# SkateboardIntegrated.net
KiCad netlist of a schematic drawn in EAGLE
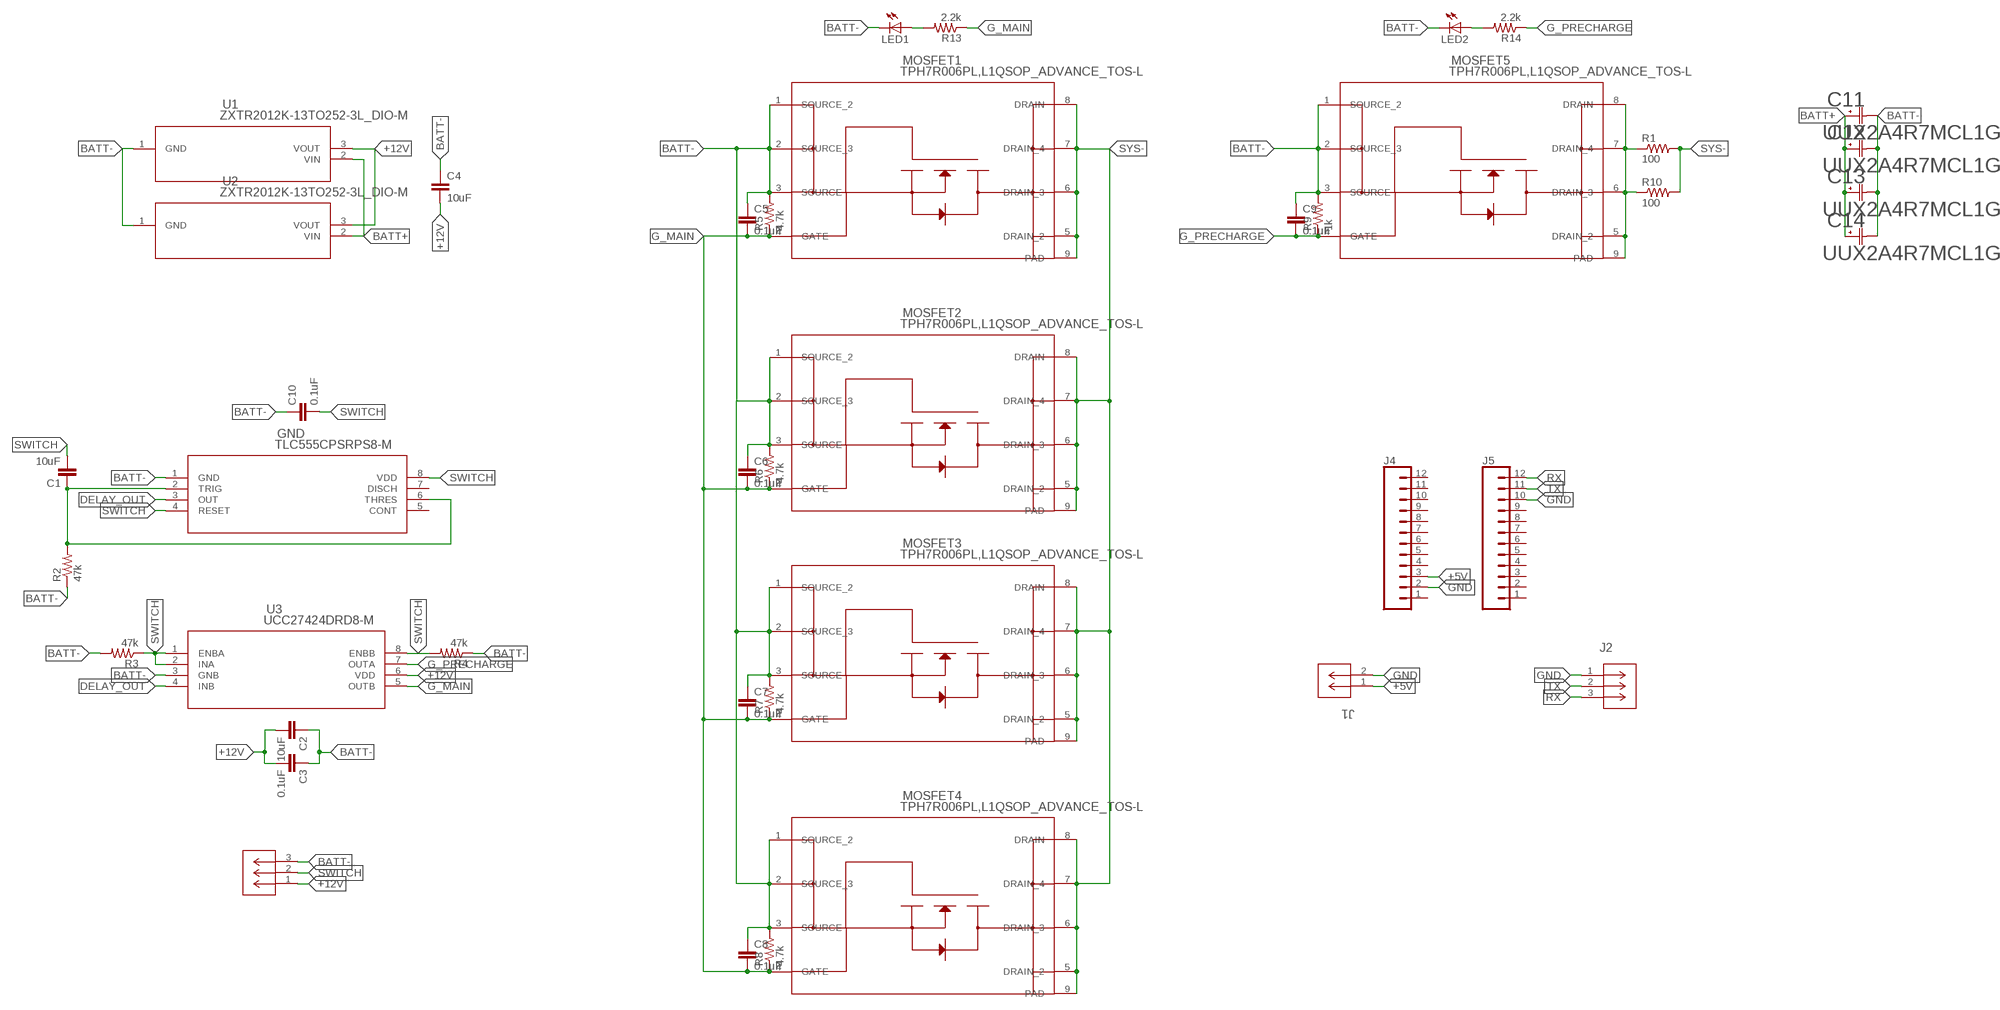
[diagram p0: schematic, sheet 1]

(export (version "E")
  (design (tool "Eeschema 10.0.6"))
  (components
    (comp (ref "C1")
      (value "10uF")
      (footprint "eagle-import:0805")
      (libsource (lib "eagle-import") (part "10UF-0805-10V-10%"))
    )
    (comp (ref "C2")
      (value "10uF")
      (footprint "eagle-import:0805")
      (libsource (lib "eagle-import") (part "10UF-0805-10V-10%"))
    )
    (comp (ref "C3")
      (value "0.1uF")
      (footprint "eagle-import:0805")
      (libsource (lib "eagle-import") (part "10UF-0805-10V-10%"))
    )
    (comp (ref "C4")
      (value "10uF")
      (footprint "eagle-import:0805")
      (libsource (lib "eagle-import") (part "10UF-0805-10V-10%"))
    )
    (comp (ref "C5")
      (value "0.1uF")
      (footprint "eagle-import:0805")
      (libsource (lib "eagle-import") (part "10UF-0805-10V-10%"))
    )
    (comp (ref "C6")
      (value "0.1uF")
      (footprint "eagle-import:0805")
      (libsource (lib "eagle-import") (part "10UF-0805-10V-10%"))
    )
    (comp (ref "C7")
      (value "0.1uF")
      (footprint "eagle-import:0805")
      (libsource (lib "eagle-import") (part "10UF-0805-10V-10%"))
    )
    (comp (ref "C8")
      (value "0.1uF")
      (footprint "eagle-import:0805")
      (libsource (lib "eagle-import") (part "10UF-0805-10V-10%"))
    )
    (comp (ref "C9")
      (value "0.1uF")
      (footprint "eagle-import:0805")
      (libsource (lib "eagle-import") (part "10UF-0805-10V-10%"))
    )
    (comp (ref "C10")
      (value "0.1uF")
      (footprint "eagle-import:0805")
      (libsource (lib "eagle-import") (part "10UF-0805-10V-10%"))
    )
    (comp (ref "C11")
      (value "UUX2A4R7MCL1GS")
      (footprint "eagle-import:CAP_UCD_8X6P2_NCH")
      (fields (field (name "COPYRIGHT") "Copyright (C) 2022 Ultra Librarian. All rights reserved."))
      (libsource (lib "eagle-import") (part "UUX2A4R7MCL1GS"))
    )
    (comp (ref "C12")
      (value "UUX2A4R7MCL1GS")
      (footprint "eagle-import:CAP_UCD_8X6P2_NCH")
      (fields (field (name "COPYRIGHT") "Copyright (C) 2022 Ultra Librarian. All rights reserved."))
      (libsource (lib "eagle-import") (part "UUX2A4R7MCL1GS"))
    )
    (comp (ref "C13")
      (value "UUX2A4R7MCL1GS")
      (footprint "eagle-import:CAP_UCD_8X6P2_NCH")
      (fields (field (name "COPYRIGHT") "Copyright (C) 2022 Ultra Librarian. All rights reserved."))
      (libsource (lib "eagle-import") (part "UUX2A4R7MCL1GS"))
    )
    (comp (ref "C14")
      (value "UUX2A4R7MCL1GS")
      (footprint "eagle-import:CAP_UCD_8X6P2_NCH")
      (fields (field (name "COPYRIGHT") "Copyright (C) 2022 Ultra Librarian. All rights reserved."))
      (libsource (lib "eagle-import") (part "UUX2A4R7MCL1GS"))
    )
    (comp (ref "GND")
      (value "TLC555CPSRPS8-M")
      (footprint "eagle-import:PS8-M")
      (fields
        (field (name "MANUFACTURER_PART_NUMBER") "TLC555CPSR")
        (field (name "COPYRIGHT") "Copyright (C) 2022 Ultra Librarian. All rights reserved.")
      )
      (libsource (lib "eagle-import") (part "TLC555CPSRPS8-M"))
    )
    (comp (ref "J1")
      (value "1775470-2")
      (footprint "eagle-import:CONN2_1775470-2_TEC")
      (fields (field (name "COPYRIGHT") "Copyright (C) 2022 Ultra Librarian. All rights reserved."))
      (libsource (lib "eagle-import") (part "1775470-2"))
    )
    (comp (ref "J2")
      (value "1775470-3")
      (footprint "eagle-import:CONN3_1775470-3_TEC")
      (fields (field (name "COPYRIGHT") "Copyright (C) 2022 Ultra Librarian. All rights reserved."))
      (libsource (lib "eagle-import") (part "1775470-3"))
    )
    (comp (ref "J3")
      (value "1775470-3")
      (footprint "eagle-import:CONN3_1775470-3_TEC")
      (fields (field (name "COPYRIGHT") "Copyright (C) 2022 Ultra Librarian. All rights reserved."))
      (libsource (lib "eagle-import") (part "1775470-3"))
    )
    (comp (ref "J4")
      (value "CONN_12SMD_ALT")
      (footprint "eagle-import:1X12_SMD_ALT")
      (libsource (lib "eagle-import") (part "CONN_12SMD_ALT"))
    )
    (comp (ref "J5")
      (value "CONN_12SMD_ALT")
      (footprint "eagle-import:1X12_SMD_ALT")
      (libsource (lib "eagle-import") (part "CONN_12SMD_ALT"))
    )
    (comp (ref "LED1")
      (value "LEDCHIPLED_0805")
      (footprint "eagle-import:CHIPLED_0805")
      (libsource (lib "eagle-import") (part "LEDCHIPLED_0805"))
    )
    (comp (ref "LED2")
      (value "LEDCHIPLED_0805")
      (footprint "eagle-import:CHIPLED_0805")
      (libsource (lib "eagle-import") (part "LEDCHIPLED_0805"))
    )
    (comp (ref "MOSFET1")
      (value "TPH7R006PL,L1QSOP_ADVANCE_TOS-L")
      (footprint "eagle-import:SOP_ADVANCE_TOS-L")
      (fields
        (field (name "MANUFACTURER_PART_NUMBER") "TPH7R006PL,L1Q")
        (field (name "COPYRIGHT") "Copyright (C) 2022 Ultra Librarian. All rights reserved.")
      )
      (libsource (lib "eagle-import") (part "TPH7R006PL,L1QSOP_ADVANCE_TOS-L"))
    )
    (comp (ref "MOSFET2")
      (value "TPH7R006PL,L1QSOP_ADVANCE_TOS-L")
      (footprint "eagle-import:SOP_ADVANCE_TOS-L")
      (fields
        (field (name "MANUFACTURER_PART_NUMBER") "TPH7R006PL,L1Q")
        (field (name "COPYRIGHT") "Copyright (C) 2022 Ultra Librarian. All rights reserved.")
      )
      (libsource (lib "eagle-import") (part "TPH7R006PL,L1QSOP_ADVANCE_TOS-L"))
    )
    (comp (ref "MOSFET3")
      (value "TPH7R006PL,L1QSOP_ADVANCE_TOS-L")
      (footprint "eagle-import:SOP_ADVANCE_TOS-L")
      (fields
        (field (name "MANUFACTURER_PART_NUMBER") "TPH7R006PL,L1Q")
        (field (name "COPYRIGHT") "Copyright (C) 2022 Ultra Librarian. All rights reserved.")
      )
      (libsource (lib "eagle-import") (part "TPH7R006PL,L1QSOP_ADVANCE_TOS-L"))
    )
    (comp (ref "MOSFET4")
      (value "TPH7R006PL,L1QSOP_ADVANCE_TOS-L")
      (footprint "eagle-import:SOP_ADVANCE_TOS-L")
      (fields
        (field (name "MANUFACTURER_PART_NUMBER") "TPH7R006PL,L1Q")
        (field (name "COPYRIGHT") "Copyright (C) 2022 Ultra Librarian. All rights reserved.")
      )
      (libsource (lib "eagle-import") (part "TPH7R006PL,L1QSOP_ADVANCE_TOS-L"))
    )
    (comp (ref "MOSFET5")
      (value "TPH7R006PL,L1QSOP_ADVANCE_TOS-L")
      (footprint "eagle-import:SOP_ADVANCE_TOS-L")
      (fields
        (field (name "MANUFACTURER_PART_NUMBER") "TPH7R006PL,L1Q")
        (field (name "COPYRIGHT") "Copyright (C) 2022 Ultra Librarian. All rights reserved.")
      )
      (libsource (lib "eagle-import") (part "TPH7R006PL,L1QSOP_ADVANCE_TOS-L"))
    )
    (comp (ref "R1")
      (value "100")
      (footprint "eagle-import:R2512")
      (libsource (lib "eagle-import") (part "R-US_R2512"))
    )
    (comp (ref "R2")
      (value "47k")
      (footprint "eagle-import:R0805")
      (libsource (lib "eagle-import") (part "R-US_R0805"))
    )
    (comp (ref "R3")
      (value "47k")
      (footprint "eagle-import:R0805")
      (libsource (lib "eagle-import") (part "R-US_R0805"))
    )
    (comp (ref "R4")
      (value "47k")
      (footprint "eagle-import:R0805")
      (libsource (lib "eagle-import") (part "R-US_R0805"))
    )
    (comp (ref "R5")
      (value "4.7k")
      (footprint "eagle-import:R0805")
      (libsource (lib "eagle-import") (part "R-US_R0805"))
    )
    (comp (ref "R6")
      (value "4.7k")
      (footprint "eagle-import:R0805")
      (libsource (lib "eagle-import") (part "R-US_R0805"))
    )
    (comp (ref "R7")
      (value "4.7k")
      (footprint "eagle-import:R0805")
      (libsource (lib "eagle-import") (part "R-US_R0805"))
    )
    (comp (ref "R8")
      (value "4.7k")
      (footprint "eagle-import:R0805")
      (libsource (lib "eagle-import") (part "R-US_R0805"))
    )
    (comp (ref "R9")
      (value "1k")
      (footprint "eagle-import:R0805")
      (libsource (lib "eagle-import") (part "R-US_R0805"))
    )
    (comp (ref "R10")
      (value "100")
      (footprint "eagle-import:R2512")
      (libsource (lib "eagle-import") (part "R-US_R2512"))
    )
    (comp (ref "R13")
      (value "2.2k")
      (footprint "eagle-import:R0805")
      (libsource (lib "eagle-import") (part "R-US_R0805"))
    )
    (comp (ref "R14")
      (value "2.2k")
      (footprint "eagle-import:R0805")
      (libsource (lib "eagle-import") (part "R-US_R0805"))
    )
    (comp (ref "U1")
      (value "ZXTR2012K-13TO252-3L_DIO-M")
      (footprint "eagle-import:TO252-3L_DIO-M")
      (fields
        (field (name "MANUFACTURER_PART_NUMBER") "ZXTR2012K-13")
        (field (name "COPYRIGHT") "Copyright (C) 2022 Ultra Librarian. All rights reserved.")
      )
      (libsource (lib "eagle-import") (part "ZXTR2012K-13TO252-3L_DIO-M"))
    )
    (comp (ref "U2")
      (value "ZXTR2012K-13TO252-3L_DIO-M")
      (footprint "eagle-import:TO252-3L_DIO-M")
      (fields
        (field (name "MANUFACTURER_PART_NUMBER") "ZXTR2012K-13")
        (field (name "COPYRIGHT") "Copyright (C) 2022 Ultra Librarian. All rights reserved.")
      )
      (libsource (lib "eagle-import") (part "ZXTR2012K-13TO252-3L_DIO-M"))
    )
    (comp (ref "U3")
      (value "UCC27424DRD8-M")
      (footprint "eagle-import:D8-M")
      (fields
        (field (name "MANUFACTURER_PART_NUMBER") "UCC27424DR")
        (field (name "COPYRIGHT") "Copyright (C) 2022 Ultra Librarian. All rights reserved.")
      )
      (libsource (lib "eagle-import") (part "UCC27424DRD8-M"))
    )
  )
  (nets
    (net (code "1") (name "+5V") (class "Default")
      (node (ref "J1") (pin "1") (pinfunction "1_1") (pintype "passive"))
      (node (ref "J4") (pin "3") (pinfunction "3_3") (pintype "passive"))
    )
    (net (code "2") (name "+12V") (class "Default")
      (node (ref "C2") (pin "2") (pinfunction "2_2") (pintype "passive"))
      (node (ref "C3") (pin "2") (pinfunction "2_2") (pintype "passive"))
      (node (ref "C4") (pin "2") (pinfunction "2_2") (pintype "passive"))
      (node (ref "J3") (pin "1") (pinfunction "1_1") (pintype "passive"))
      (node (ref "U1") (pin "3") (pinfunction "VOUT_3") (pintype "output"))
      (node (ref "U2") (pin "3") (pinfunction "VOUT_3") (pintype "output"))
      (node (ref "U3") (pin "6") (pinfunction "VDD_6") (pintype "power_in"))
    )
    (net (code "3") (name "BATT+") (class "Default")
      (node (ref "C11") (pin "1") (pinfunction "1_1") (pintype "passive"))
      (node (ref "C12") (pin "1") (pinfunction "1_1") (pintype "passive"))
      (node (ref "C13") (pin "1") (pinfunction "1_1") (pintype "passive"))
      (node (ref "C14") (pin "1") (pinfunction "1_1") (pintype "passive"))
      (node (ref "U1") (pin "2") (pinfunction "VIN_2") (pintype "input"))
      (node (ref "U2") (pin "2") (pinfunction "VIN_2") (pintype "input"))
    )
    (net (code "4") (name "BATT-") (class "Default")
      (node (ref "C10") (pin "1") (pinfunction "1_1") (pintype "passive"))
      (node (ref "C11") (pin "2") (pinfunction "2_2") (pintype "passive"))
      (node (ref "C12") (pin "2") (pinfunction "2_2") (pintype "passive"))
      (node (ref "C13") (pin "2") (pinfunction "2_2") (pintype "passive"))
      (node (ref "C14") (pin "2") (pinfunction "2_2") (pintype "passive"))
      (node (ref "C2") (pin "1") (pinfunction "1_1") (pintype "passive"))
      (node (ref "C3") (pin "1") (pinfunction "1_1") (pintype "passive"))
      (node (ref "C4") (pin "1") (pinfunction "1_1") (pintype "passive"))
      (node (ref "C5") (pin "1") (pinfunction "1_1") (pintype "passive"))
      (node (ref "C6") (pin "1") (pinfunction "1_1") (pintype "passive"))
      (node (ref "C7") (pin "1") (pinfunction "1_1") (pintype "passive"))
      (node (ref "C8") (pin "1") (pinfunction "1_1") (pintype "passive"))
      (node (ref "C9") (pin "1") (pinfunction "1_1") (pintype "passive"))
      (node (ref "GND") (pin "1") (pinfunction "GND_1") (pintype "power_in"))
      (node (ref "J3") (pin "3") (pinfunction "3_3") (pintype "passive"))
      (node (ref "LED1") (pin "C") (pinfunction "C_C") (pintype "passive"))
      (node (ref "LED2") (pin "C") (pinfunction "C_C") (pintype "passive"))
      (node (ref "MOSFET1") (pin "1") (pinfunction "SOURCE_2_1") (pintype "passive"))
      (node (ref "MOSFET1") (pin "2") (pinfunction "SOURCE_3_2") (pintype "passive"))
      (node (ref "MOSFET1") (pin "3") (pinfunction "SOURCE_3") (pintype "passive"))
      (node (ref "MOSFET2") (pin "1") (pinfunction "SOURCE_2_1") (pintype "passive"))
      (node (ref "MOSFET2") (pin "2") (pinfunction "SOURCE_3_2") (pintype "passive"))
      (node (ref "MOSFET2") (pin "3") (pinfunction "SOURCE_3") (pintype "passive"))
      (node (ref "MOSFET3") (pin "1") (pinfunction "SOURCE_2_1") (pintype "passive"))
      (node (ref "MOSFET3") (pin "2") (pinfunction "SOURCE_3_2") (pintype "passive"))
      (node (ref "MOSFET3") (pin "3") (pinfunction "SOURCE_3") (pintype "passive"))
      (node (ref "MOSFET4") (pin "1") (pinfunction "SOURCE_2_1") (pintype "passive"))
      (node (ref "MOSFET4") (pin "2") (pinfunction "SOURCE_3_2") (pintype "passive"))
      (node (ref "MOSFET4") (pin "3") (pinfunction "SOURCE_3") (pintype "passive"))
      (node (ref "MOSFET5") (pin "1") (pinfunction "SOURCE_2_1") (pintype "passive"))
      (node (ref "MOSFET5") (pin "2") (pinfunction "SOURCE_3_2") (pintype "passive"))
      (node (ref "MOSFET5") (pin "3") (pinfunction "SOURCE_3") (pintype "passive"))
      (node (ref "R2") (pin "1") (pinfunction "1_1") (pintype "passive"))
      (node (ref "R3") (pin "2") (pinfunction "2_2") (pintype "passive"))
      (node (ref "R4") (pin "1") (pinfunction "1_1") (pintype "passive"))
      (node (ref "R5") (pin "2") (pinfunction "2_2") (pintype "passive"))
      (node (ref "R6") (pin "2") (pinfunction "2_2") (pintype "passive"))
      (node (ref "R7") (pin "2") (pinfunction "2_2") (pintype "passive"))
      (node (ref "R8") (pin "2") (pinfunction "2_2") (pintype "passive"))
      (node (ref "R9") (pin "2") (pinfunction "2_2") (pintype "passive"))
      (node (ref "U1") (pin "1") (pinfunction "GND_1") (pintype "power_in"))
      (node (ref "U2") (pin "1") (pinfunction "GND_1") (pintype "power_in"))
      (node (ref "U3") (pin "3") (pinfunction "GNB_3") (pintype "power_in"))
    )
    (net (code "5") (name "DELAY_OUT") (class "Default")
      (node (ref "GND") (pin "3") (pinfunction "OUT_3") (pintype "output"))
      (node (ref "U3") (pin "4") (pinfunction "INB_4") (pintype "input"))
    )
    (net (code "6") (name "GND") (class "Default")
      (node (ref "J1") (pin "2") (pinfunction "2_2") (pintype "passive"))
      (node (ref "J2") (pin "1") (pinfunction "1_1") (pintype "passive"))
      (node (ref "J4") (pin "2") (pinfunction "2_2") (pintype "passive"))
      (node (ref "J5") (pin "10") (pinfunction "10_10") (pintype "passive"))
    )
    (net (code "7") (name "G_MAIN") (class "Default")
      (node (ref "C5") (pin "2") (pinfunction "2_2") (pintype "passive"))
      (node (ref "C6") (pin "2") (pinfunction "2_2") (pintype "passive"))
      (node (ref "C7") (pin "2") (pinfunction "2_2") (pintype "passive"))
      (node (ref "C8") (pin "2") (pinfunction "2_2") (pintype "passive"))
      (node (ref "MOSFET1") (pin "4") (pinfunction "GATE_4") (pintype "passive"))
      (node (ref "MOSFET2") (pin "4") (pinfunction "GATE_4") (pintype "passive"))
      (node (ref "MOSFET3") (pin "4") (pinfunction "GATE_4") (pintype "passive"))
      (node (ref "MOSFET4") (pin "4") (pinfunction "GATE_4") (pintype "passive"))
      (node (ref "R13") (pin "1") (pinfunction "1_1") (pintype "passive"))
      (node (ref "R5") (pin "1") (pinfunction "1_1") (pintype "passive"))
      (node (ref "R6") (pin "1") (pinfunction "1_1") (pintype "passive"))
      (node (ref "R7") (pin "1") (pinfunction "1_1") (pintype "passive"))
      (node (ref "R8") (pin "1") (pinfunction "1_1") (pintype "passive"))
      (node (ref "U3") (pin "5") (pinfunction "OUTB_5") (pintype "output"))
    )
    (net (code "8") (name "G_PRECHARGE") (class "Default")
      (node (ref "C9") (pin "2") (pinfunction "2_2") (pintype "passive"))
      (node (ref "MOSFET5") (pin "4") (pinfunction "GATE_4") (pintype "passive"))
      (node (ref "R14") (pin "1") (pinfunction "1_1") (pintype "passive"))
      (node (ref "R9") (pin "1") (pinfunction "1_1") (pintype "passive"))
      (node (ref "U3") (pin "7") (pinfunction "OUTA_7") (pintype "output"))
    )
    (net (code "9") (name "Net-(GND-THRES)") (class "Default")
      (node (ref "C1") (pin "1") (pinfunction "1_1") (pintype "passive"))
      (node (ref "GND") (pin "2") (pinfunction "TRIG_2") (pintype "passive"))
      (node (ref "GND") (pin "6") (pinfunction "THRES_6") (pintype "passive"))
      (node (ref "R2") (pin "2") (pinfunction "2_2") (pintype "passive"))
    )
    (net (code "10") (name "Net-(LED1-PadA)") (class "Default")
      (node (ref "LED1") (pin "A") (pinfunction "A_A") (pintype "passive"))
      (node (ref "R13") (pin "2") (pinfunction "2_2") (pintype "passive"))
    )
    (net (code "11") (name "Net-(LED2-PadA)") (class "Default")
      (node (ref "LED2") (pin "A") (pinfunction "A_A") (pintype "passive"))
      (node (ref "R14") (pin "2") (pinfunction "2_2") (pintype "passive"))
    )
    (net (code "12") (name "Net-(MOSFET5-DRAIN)") (class "Default")
      (node (ref "MOSFET5") (pin "5") (pinfunction "DRAIN_2_5") (pintype "passive"))
      (node (ref "MOSFET5") (pin "6") (pinfunction "DRAIN_3_6") (pintype "passive"))
      (node (ref "MOSFET5") (pin "7") (pinfunction "DRAIN_4_7") (pintype "passive"))
      (node (ref "MOSFET5") (pin "8") (pinfunction "DRAIN_8") (pintype "passive"))
      (node (ref "MOSFET5") (pin "9") (pinfunction "PAD_9") (pintype "bidirectional"))
      (node (ref "R1") (pin "1") (pinfunction "1_1") (pintype "passive"))
      (node (ref "R10") (pin "1") (pinfunction "1_1") (pintype "passive"))
    )
    (net (code "13") (name "RX") (class "Default")
      (node (ref "J2") (pin "3") (pinfunction "3_3") (pintype "passive"))
      (node (ref "J5") (pin "12") (pinfunction "12_12") (pintype "passive"))
    )
    (net (code "14") (name "SWITCH") (class "Default")
      (node (ref "C1") (pin "2") (pinfunction "2_2") (pintype "passive"))
      (node (ref "C10") (pin "2") (pinfunction "2_2") (pintype "passive"))
      (node (ref "GND") (pin "4") (pinfunction "RESET_4") (pintype "passive"))
      (node (ref "GND") (pin "8") (pinfunction "VDD_8") (pintype "power_in"))
      (node (ref "J3") (pin "2") (pinfunction "2_2") (pintype "passive"))
      (node (ref "R3") (pin "1") (pinfunction "1_1") (pintype "passive"))
      (node (ref "R4") (pin "2") (pinfunction "2_2") (pintype "passive"))
      (node (ref "U3") (pin "1") (pinfunction "ENBA_1") (pintype "input"))
      (node (ref "U3") (pin "2") (pinfunction "INA_2") (pintype "input"))
      (node (ref "U3") (pin "8") (pinfunction "ENBB_8") (pintype "input"))
    )
    (net (code "15") (name "SYS-") (class "Default")
      (node (ref "MOSFET1") (pin "5") (pinfunction "DRAIN_2_5") (pintype "passive"))
      (node (ref "MOSFET1") (pin "6") (pinfunction "DRAIN_3_6") (pintype "passive"))
      (node (ref "MOSFET1") (pin "7") (pinfunction "DRAIN_4_7") (pintype "passive"))
      (node (ref "MOSFET1") (pin "8") (pinfunction "DRAIN_8") (pintype "passive"))
      (node (ref "MOSFET1") (pin "9") (pinfunction "PAD_9") (pintype "bidirectional"))
      (node (ref "MOSFET2") (pin "5") (pinfunction "DRAIN_2_5") (pintype "passive"))
      (node (ref "MOSFET2") (pin "6") (pinfunction "DRAIN_3_6") (pintype "passive"))
      (node (ref "MOSFET2") (pin "7") (pinfunction "DRAIN_4_7") (pintype "passive"))
      (node (ref "MOSFET2") (pin "8") (pinfunction "DRAIN_8") (pintype "passive"))
      (node (ref "MOSFET2") (pin "9") (pinfunction "PAD_9") (pintype "bidirectional"))
      (node (ref "MOSFET3") (pin "5") (pinfunction "DRAIN_2_5") (pintype "passive"))
      (node (ref "MOSFET3") (pin "6") (pinfunction "DRAIN_3_6") (pintype "passive"))
      (node (ref "MOSFET3") (pin "7") (pinfunction "DRAIN_4_7") (pintype "passive"))
      (node (ref "MOSFET3") (pin "8") (pinfunction "DRAIN_8") (pintype "passive"))
      (node (ref "MOSFET3") (pin "9") (pinfunction "PAD_9") (pintype "bidirectional"))
      (node (ref "MOSFET4") (pin "5") (pinfunction "DRAIN_2_5") (pintype "passive"))
      (node (ref "MOSFET4") (pin "6") (pinfunction "DRAIN_3_6") (pintype "passive"))
      (node (ref "MOSFET4") (pin "7") (pinfunction "DRAIN_4_7") (pintype "passive"))
      (node (ref "MOSFET4") (pin "8") (pinfunction "DRAIN_8") (pintype "passive"))
      (node (ref "MOSFET4") (pin "9") (pinfunction "PAD_9") (pintype "bidirectional"))
      (node (ref "R1") (pin "2") (pinfunction "2_2") (pintype "passive"))
      (node (ref "R10") (pin "2") (pinfunction "2_2") (pintype "passive"))
    )
    (net (code "16") (name "TX") (class "Default")
      (node (ref "J2") (pin "2") (pinfunction "2_2") (pintype "passive"))
      (node (ref "J5") (pin "11") (pinfunction "11_11") (pintype "passive"))
    )
    (net (code "17") (name "unconnected-(GND-CONT-Pad5)") (class "Default")
      (node (ref "GND") (pin "5") (pinfunction "CONT_5") (pintype "passive"))
    )
    (net (code "18") (name "unconnected-(GND-DISCH-Pad7)") (class "Default")
      (node (ref "GND") (pin "7") (pinfunction "DISCH_7") (pintype "passive"))
    )
    (net (code "19") (name "unconnected-(J4-Pad1)") (class "Default")
      (node (ref "J4") (pin "1") (pinfunction "1_1") (pintype "passive"))
    )
    (net (code "20") (name "unconnected-(J4-Pad4)") (class "Default")
      (node (ref "J4") (pin "4") (pinfunction "4_4") (pintype "passive"))
    )
    (net (code "21") (name "unconnected-(J4-Pad5)") (class "Default")
      (node (ref "J4") (pin "5") (pinfunction "5_5") (pintype "passive"))
    )
    (net (code "22") (name "unconnected-(J4-Pad6)") (class "Default")
      (node (ref "J4") (pin "6") (pinfunction "6_6") (pintype "passive"))
    )
    (net (code "23") (name "unconnected-(J4-Pad7)") (class "Default")
      (node (ref "J4") (pin "7") (pinfunction "7_7") (pintype "passive"))
    )
    (net (code "24") (name "unconnected-(J4-Pad8)") (class "Default")
      (node (ref "J4") (pin "8") (pinfunction "8_8") (pintype "passive"))
    )
    (net (code "25") (name "unconnected-(J4-Pad9)") (class "Default")
      (node (ref "J4") (pin "9") (pinfunction "9_9") (pintype "passive"))
    )
    (net (code "26") (name "unconnected-(J4-Pad10)") (class "Default")
      (node (ref "J4") (pin "10") (pinfunction "10_10") (pintype "passive"))
    )
    (net (code "27") (name "unconnected-(J4-Pad11)") (class "Default")
      (node (ref "J4") (pin "11") (pinfunction "11_11") (pintype "passive"))
    )
    (net (code "28") (name "unconnected-(J4-Pad12)") (class "Default")
      (node (ref "J4") (pin "12") (pinfunction "12_12") (pintype "passive"))
    )
    (net (code "29") (name "unconnected-(J5-Pad1)") (class "Default")
      (node (ref "J5") (pin "1") (pinfunction "1_1") (pintype "passive"))
    )
    (net (code "30") (name "unconnected-(J5-Pad2)") (class "Default")
      (node (ref "J5") (pin "2") (pinfunction "2_2") (pintype "passive"))
    )
    (net (code "31") (name "unconnected-(J5-Pad3)") (class "Default")
      (node (ref "J5") (pin "3") (pinfunction "3_3") (pintype "passive"))
    )
    (net (code "32") (name "unconnected-(J5-Pad4)") (class "Default")
      (node (ref "J5") (pin "4") (pinfunction "4_4") (pintype "passive"))
    )
    (net (code "33") (name "unconnected-(J5-Pad5)") (class "Default")
      (node (ref "J5") (pin "5") (pinfunction "5_5") (pintype "passive"))
    )
    (net (code "34") (name "unconnected-(J5-Pad6)") (class "Default")
      (node (ref "J5") (pin "6") (pinfunction "6_6") (pintype "passive"))
    )
    (net (code "35") (name "unconnected-(J5-Pad7)") (class "Default")
      (node (ref "J5") (pin "7") (pinfunction "7_7") (pintype "passive"))
    )
    (net (code "36") (name "unconnected-(J5-Pad8)") (class "Default")
      (node (ref "J5") (pin "8") (pinfunction "8_8") (pintype "passive"))
    )
    (net (code "37") (name "unconnected-(J5-Pad9)") (class "Default")
      (node (ref "J5") (pin "9") (pinfunction "9_9") (pintype "passive"))
    )
  )
)
